# OneLedBlinker.net
KiCad netlist of a schematic drawn in EAGLE
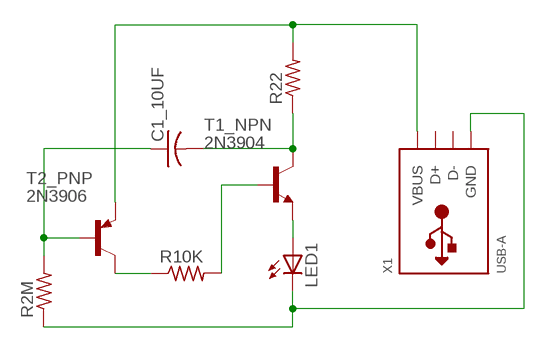
[diagram p0: schematic, sheet 1]

(export (version "E")
  (design (tool "Eeschema 10.0.6"))
  (components
    (comp (ref "C1_10UF")
      (value "C-US025-030X050")
      (footprint "eagle-import:C025-030X050")
      (libsource (lib "eagle-import") (part "C-US025-030X050"))
    )
    (comp (ref "LED1")
      (value "LED5MM")
      (footprint "eagle-import:LED5MM")
      (libsource (lib "eagle-import") (part "LED5MM"))
    )
    (comp (ref "R2M")
      (value "R-US_0207/10")
      (footprint "eagle-import:0207_10")
      (libsource (lib "eagle-import") (part "R-US_0207/10"))
    )
    (comp (ref "R10K")
      (value "R-US_0207/10")
      (footprint "eagle-import:0207_10")
      (libsource (lib "eagle-import") (part "R-US_0207/10"))
    )
    (comp (ref "R22")
      (value "R-US_0207/10")
      (footprint "eagle-import:0207_10")
      (libsource (lib "eagle-import") (part "R-US_0207/10"))
    )
    (comp (ref "T1_NPN")
      (value "2N3904")
      (footprint "eagle-import:TO92")
      (libsource (lib "eagle-import") (part "2N3904"))
    )
    (comp (ref "T2_PNP")
      (value "2N3906")
      (footprint "eagle-import:TO92")
      (libsource (lib "eagle-import") (part "2N3906"))
    )
    (comp (ref "X1")
      (value "USB-A")
      (footprint "eagle-import:MOLEX_480371000")
      (libsource (lib "eagle-import") (part "USB-A"))
    )
  )
  (nets
    (net (code "1") (name "Net-(LED1-C)") (class "Default")
      (node (ref "LED1") (pin "K") (pinfunction "C_K") (pintype "passive"))
      (node (ref "R2M") (pin "1") (pinfunction "1_1") (pintype "passive"))
      (node (ref "X1") (pin "4") (pinfunction "GND_4") (pintype "power_in"))
    )
    (net (code "2") (name "Net-(T1_NPN-B)") (class "Default")
      (node (ref "R10K") (pin "2") (pinfunction "2_2") (pintype "passive"))
      (node (ref "T1_NPN") (pin "2") (pinfunction "B_2") (pintype "passive"))
    )
    (net (code "3") (name "Net-(T1_NPN-C)") (class "Default")
      (node (ref "C1_10UF") (pin "2") (pinfunction "2_2") (pintype "passive"))
      (node (ref "R22") (pin "1") (pinfunction "1_1") (pintype "passive"))
      (node (ref "T1_NPN") (pin "1") (pinfunction "C_1") (pintype "passive"))
    )
    (net (code "4") (name "Net-(T1_NPN-E)") (class "Default")
      (node (ref "LED1") (pin "A") (pinfunction "A_A") (pintype "passive"))
      (node (ref "T1_NPN") (pin "3") (pinfunction "E_3") (pintype "passive"))
    )
    (net (code "5") (name "Net-(T2_PNP-B)") (class "Default")
      (node (ref "C1_10UF") (pin "1") (pinfunction "1_1") (pintype "passive"))
      (node (ref "R2M") (pin "2") (pinfunction "2_2") (pintype "passive"))
      (node (ref "T2_PNP") (pin "2") (pinfunction "B_2") (pintype "passive"))
    )
    (net (code "6") (name "Net-(T2_PNP-C)") (class "Default")
      (node (ref "R10K") (pin "1") (pinfunction "1_1") (pintype "passive"))
      (node (ref "T2_PNP") (pin "1") (pinfunction "C_1") (pintype "passive"))
    )
    (net (code "7") (name "Net-(T2_PNP-E)") (class "Default")
      (node (ref "R22") (pin "2") (pinfunction "2_2") (pintype "passive"))
      (node (ref "T2_PNP") (pin "3") (pinfunction "E_3") (pintype "passive"))
      (node (ref "X1") (pin "1") (pinfunction "VBUS_1") (pintype "power_in"))
    )
    (net (code "8") (name "unconnected-(X1-D+-Pad3)") (class "Default")
      (node (ref "X1") (pin "3") (pinfunction "D+_3") (pintype "bidirectional"))
    )
    (net (code "9") (name "unconnected-(X1-D--Pad2)") (class "Default")
      (node (ref "X1") (pin "2") (pinfunction "D-_2") (pintype "bidirectional"))
    )
  )
)
